# LVDS_repeater.net
KiCad netlist of a schematic drawn in Altium Designer
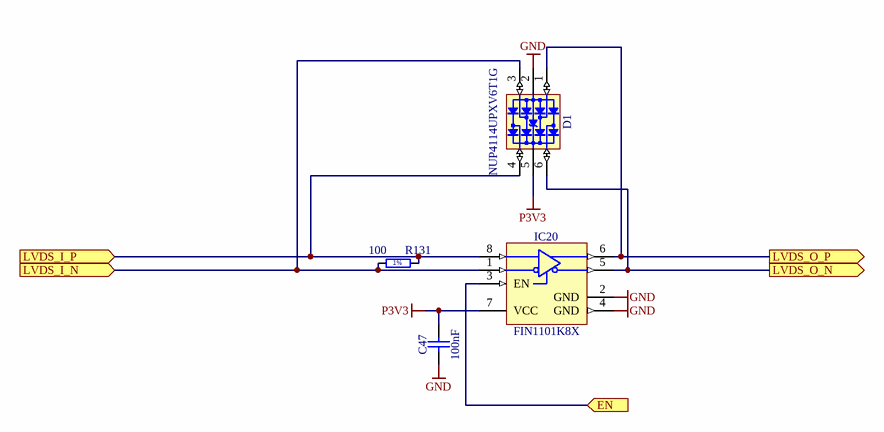
[diagram p0: LVDS_repeater.SchDoc]

(export (version "E")
  (design (tool "Eeschema 10.0.6"))
  (components
    (comp (ref "C47")
      (value "100nF")
      (footprint "CAPC1005X55N")
      (description "Non-polarised capacitor")
      (fields
        (field (name "PART NUMBER") "CC0402_100NF_16V_10%_X5R")
        (field (name "VOLTAGE") "16V")
        (field (name "AUTHOR") "CERN DEM JLC")
      )
      (libsource (lib "Capacitors") (part "Capacitor - non polarized"))
    )
    (comp (ref "D1")
      (value "NUP4114UPXV6T1G")
      (footprint "SOTFL50P160X60-6N")
      (description "ESD Protection Diodes Array (8kV) with Low Clamping Voltage")
      (fields
        (field (name "VOLTAGE") "5.5V")
        (field (name "MANUFACTURER") "ON SEMICONDUCTOR")
        (field (name "AUTHOR") "CERN DEM JLC")
      )
      (libsource (lib "ICs And Semiconductors") (part "NUP4114"))
    )
    (comp (ref "IC20")
      (value "FIN1101K8X")
      (footprint "SOP50P310X90-8N")
      (description "LVDS Single Port High Speed Repeater")
      (fields (field (name "MANUFACTURER") "FAIRCHILD SEMICONDUCTOR") (field (name "AUTHOR") "CERN DEM JLC"))
      (libsource (lib "ICs And Semiconductors") (part "FIN1101K8X"))
    )
    (comp (ref "R131")
      (value "100")
      (footprint "RESC1005X40N")
      (description "Resistor - 1%")
      (fields
        (field (name "PART NUMBER") "R0402_100R_1%_0.1W_100PPM")
        (field (name "POWER") "0.1W")
        (field (name "AUTHOR") "CERN DEM JLC")
      )
      (libsource (lib "Resistors") (part "Resistor - 1%"))
    )
  )
  (nets
    (net (code "1") (name "/EN") (class "Default")
      (node (ref "IC20") (pin "3") (pinfunction "EN_3") (pintype "input"))
    )
    (net (code "2") (name "/LVDS_I_N") (class "Default")
      (node (ref "D1") (pin "3") (pinfunction "I/O2_3") (pintype "bidirectional"))
      (node (ref "IC20") (pin "1") (pinfunction "RIN-_1") (pintype "input"))
      (node (ref "R131") (pin "1") (pinfunction "1_1") (pintype "passive"))
    )
    (net (code "3") (name "/LVDS_I_P") (class "Default")
      (node (ref "D1") (pin "4") (pinfunction "I/O3_4") (pintype "bidirectional"))
      (node (ref "IC20") (pin "8") (pinfunction "RIN+_8") (pintype "input"))
      (node (ref "R131") (pin "2") (pinfunction "2_2") (pintype "passive"))
    )
    (net (code "4") (name "/LVDS_O_N") (class "Default")
      (node (ref "D1") (pin "6") (pinfunction "I/O4_6") (pintype "bidirectional"))
      (node (ref "IC20") (pin "5") (pinfunction "DOUT-_5") (pintype "output"))
    )
    (net (code "5") (name "/LVDS_O_P") (class "Default")
      (node (ref "D1") (pin "1") (pinfunction "I/O1_1") (pintype "bidirectional"))
      (node (ref "IC20") (pin "6") (pinfunction "DOUT+_6") (pintype "output"))
    )
    (net (code "6") (name "GND") (class "Default")
      (node (ref "C47") (pin "1") (pinfunction "1_1") (pintype "passive"))
      (node (ref "D1") (pin "2") (pinfunction "GND_2") (pintype "power_in"))
      (node (ref "IC20") (pin "2") (pinfunction "GND_2") (pintype "power_in"))
      (node (ref "IC20") (pin "4") (pinfunction "GND_4") (pintype "output"))
    )
    (net (code "7") (name "P3V3") (class "Default")
      (node (ref "C47") (pin "2") (pinfunction "2_2") (pintype "passive"))
      (node (ref "D1") (pin "5") (pinfunction "VBUS_5") (pintype "power_in"))
      (node (ref "IC20") (pin "7") (pinfunction "VCC_7") (pintype "power_in"))
    )
  )
)
